# M510X.net
KiCad netlist of a schematic drawn in EAGLE
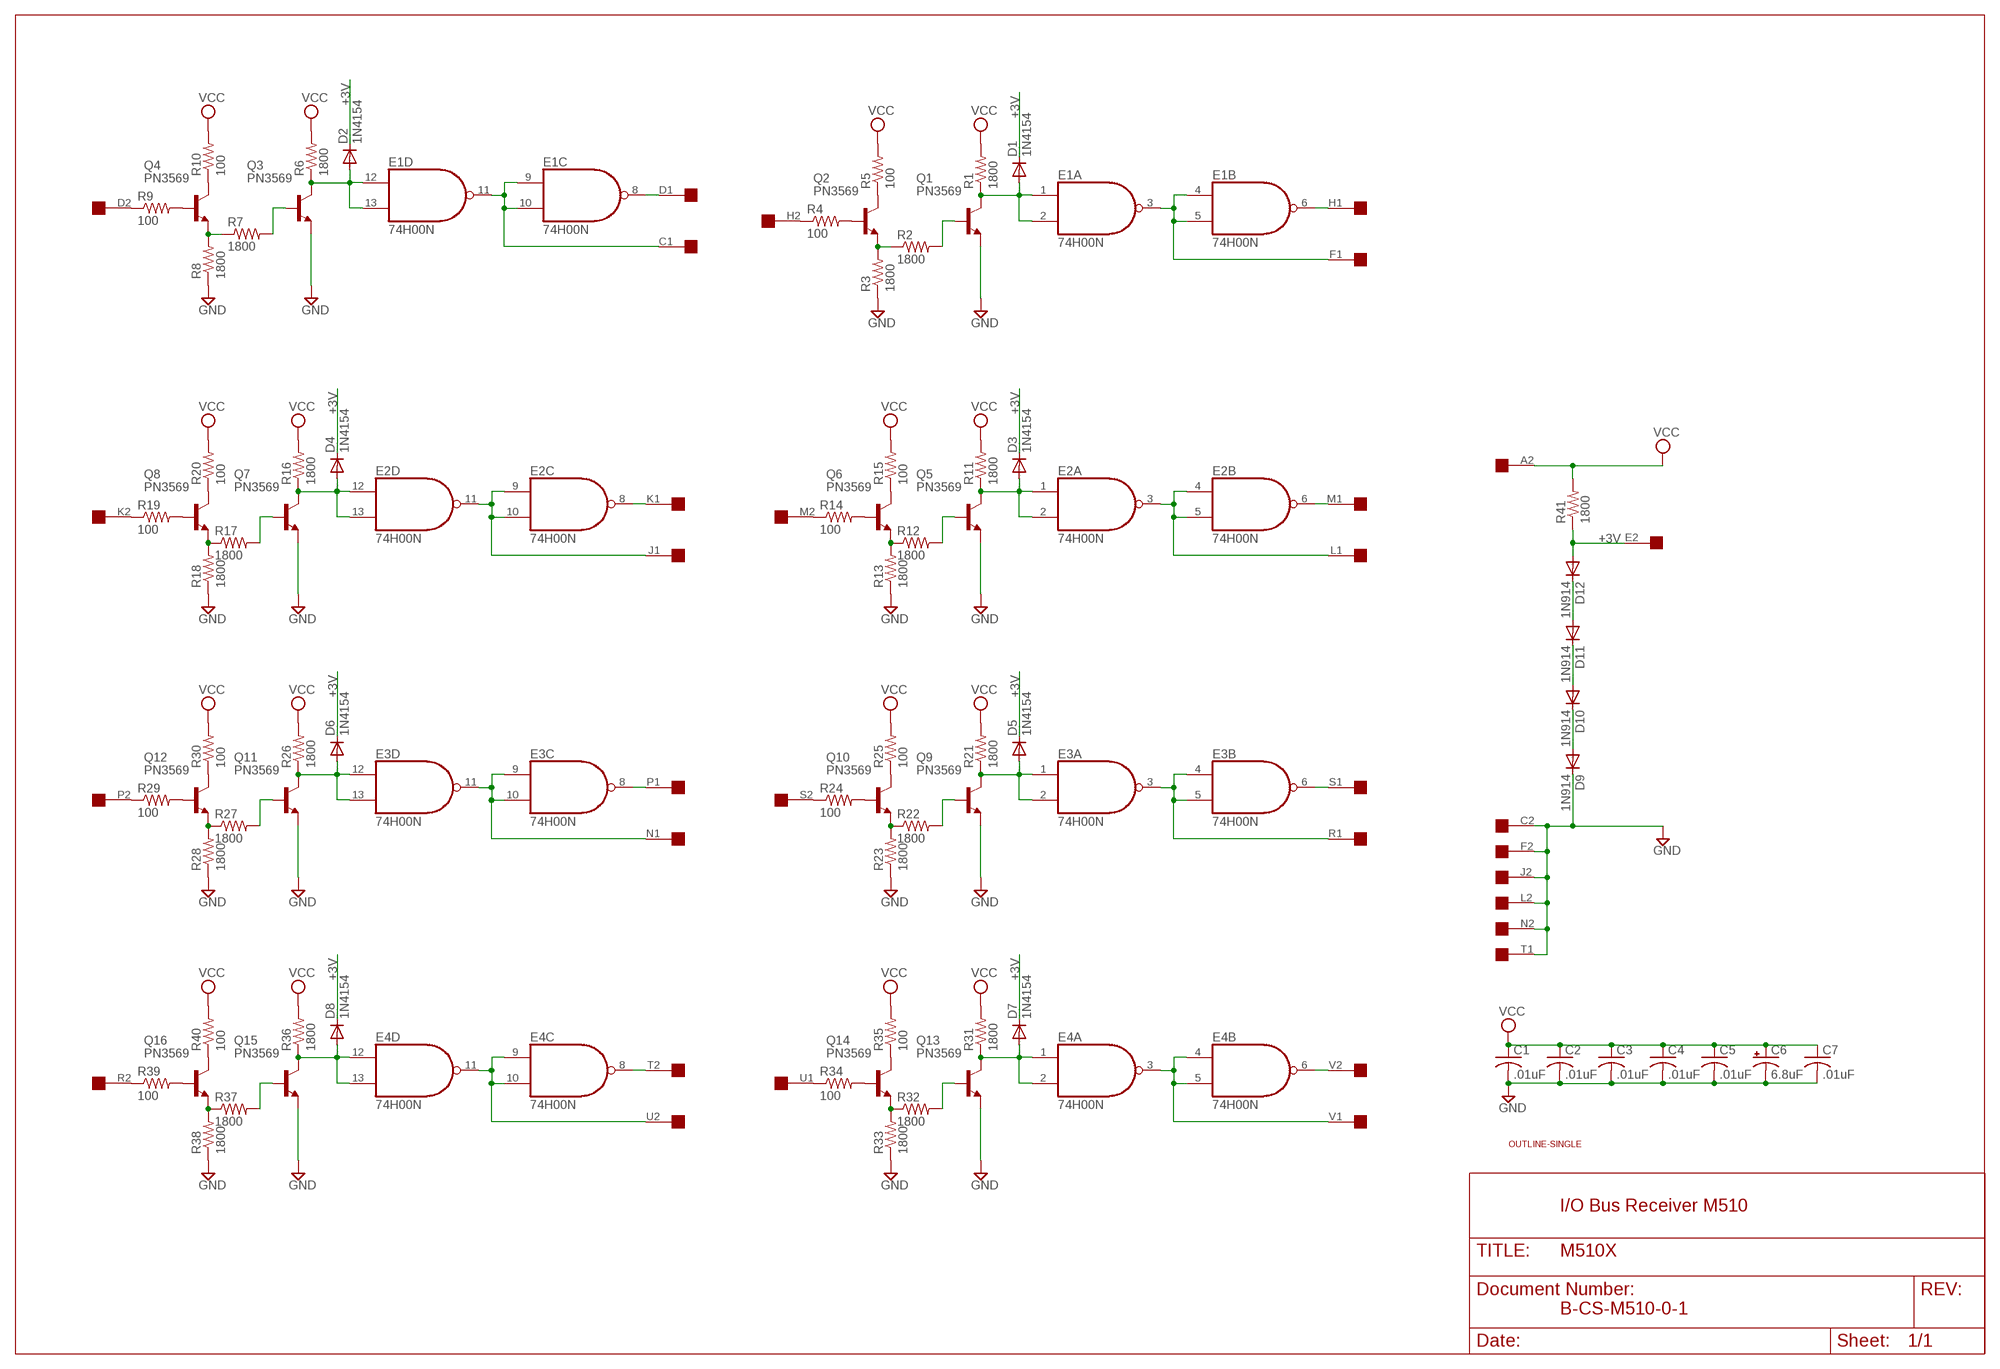
[diagram p0: schematic, sheet 1]

(export (version "E")
  (design (tool "Eeschema 10.0.6"))
  (components
    (comp (ref "C1")
      (value ".01uF")
      (footprint "eagle-import:C050-025X075")
      (libsource (lib "eagle-import") (part "C-US050-025X075"))
    )
    (comp (ref "C2")
      (value ".01uF")
      (footprint "eagle-import:C050-025X075")
      (libsource (lib "eagle-import") (part "C-US050-025X075"))
    )
    (comp (ref "C3")
      (value ".01uF")
      (footprint "eagle-import:C050-025X075")
      (libsource (lib "eagle-import") (part "C-US050-025X075"))
    )
    (comp (ref "C4")
      (value ".01uF")
      (footprint "eagle-import:C050-025X075")
      (libsource (lib "eagle-import") (part "C-US050-025X075"))
    )
    (comp (ref "C5")
      (value ".01uF")
      (footprint "eagle-import:C050-025X075")
      (libsource (lib "eagle-import") (part "C-US050-025X075"))
    )
    (comp (ref "C6")
      (value "6.8uF")
      (footprint "eagle-import:E12-8")
      (libsource (lib "eagle-import") (part "CPOL-USE20-8AXIAL"))
    )
    (comp (ref "C7")
      (value ".01uF")
      (footprint "eagle-import:C050-025X075")
      (libsource (lib "eagle-import") (part "C-US050-025X075"))
    )
    (comp (ref "D1")
      (value "1N4154")
      (footprint "eagle-import:DO35-10")
      (libsource (lib "eagle-import") (part "1N4148DO35-10"))
    )
    (comp (ref "D2")
      (value "1N4154")
      (footprint "eagle-import:DO35-10")
      (libsource (lib "eagle-import") (part "1N4148DO35-10"))
    )
    (comp (ref "D3")
      (value "1N4154")
      (footprint "eagle-import:DO35-10")
      (libsource (lib "eagle-import") (part "1N4148DO35-10"))
    )
    (comp (ref "D4")
      (value "1N4154")
      (footprint "eagle-import:DO35-10")
      (libsource (lib "eagle-import") (part "1N4148DO35-10"))
    )
    (comp (ref "D5")
      (value "1N4154")
      (footprint "eagle-import:DO35-10")
      (libsource (lib "eagle-import") (part "1N4148DO35-10"))
    )
    (comp (ref "D6")
      (value "1N4154")
      (footprint "eagle-import:DO35-10")
      (libsource (lib "eagle-import") (part "1N4148DO35-10"))
    )
    (comp (ref "D7")
      (value "1N4154")
      (footprint "eagle-import:DO35-10")
      (libsource (lib "eagle-import") (part "1N4148DO35-10"))
    )
    (comp (ref "D8")
      (value "1N4154")
      (footprint "eagle-import:DO35-10")
      (libsource (lib "eagle-import") (part "1N4148DO35-10"))
    )
    (comp (ref "D9")
      (value "1N914")
      (footprint "eagle-import:DO35-10")
      (libsource (lib "eagle-import") (part "1N4148DO35-10"))
    )
    (comp (ref "D10")
      (value "1N914")
      (footprint "eagle-import:DO35-10")
      (libsource (lib "eagle-import") (part "1N4148DO35-10"))
    )
    (comp (ref "D11")
      (value "1N914")
      (footprint "eagle-import:DO35-10")
      (libsource (lib "eagle-import") (part "1N4148DO35-10"))
    )
    (comp (ref "D12")
      (value "1N914")
      (footprint "eagle-import:DO35-10")
      (libsource (lib "eagle-import") (part "1N4148DO35-10"))
    )
    (comp (ref "E1")
      (value "74H00N")
      (footprint "eagle-import:DIL14")
      (libsource (lib "eagle-import") (part "7400N"))
    )
    (comp (ref "E2")
      (value "74H00N")
      (footprint "eagle-import:DIL14")
      (libsource (lib "eagle-import") (part "7400N"))
    )
    (comp (ref "E3")
      (value "74H00N")
      (footprint "eagle-import:DIL14")
      (libsource (lib "eagle-import") (part "7400N"))
    )
    (comp (ref "E4")
      (value "74H00N")
      (footprint "eagle-import:DIL14")
      (libsource (lib "eagle-import") (part "7400N"))
    )
    (comp (ref "EDGE1")
      (value "EDGE-2CONNECTOR")
      (footprint "eagle-import:EDGE-CON2")
      (libsource (lib "eagle-import") (part "EDGE-2CONNECTOR"))
    )
    (comp (ref "Q1")
      (value "PN3569")
      (footprint "eagle-import:TO39")
      (libsource (lib "eagle-import") (part "2N3019"))
    )
    (comp (ref "Q2")
      (value "PN3569")
      (footprint "eagle-import:TO39")
      (libsource (lib "eagle-import") (part "2N3019"))
    )
    (comp (ref "Q3")
      (value "PN3569")
      (footprint "eagle-import:TO39")
      (libsource (lib "eagle-import") (part "2N3019"))
    )
    (comp (ref "Q4")
      (value "PN3569")
      (footprint "eagle-import:TO39")
      (libsource (lib "eagle-import") (part "2N3019"))
    )
    (comp (ref "Q5")
      (value "PN3569")
      (footprint "eagle-import:TO39")
      (libsource (lib "eagle-import") (part "2N3019"))
    )
    (comp (ref "Q6")
      (value "PN3569")
      (footprint "eagle-import:TO39")
      (libsource (lib "eagle-import") (part "2N3019"))
    )
    (comp (ref "Q7")
      (value "PN3569")
      (footprint "eagle-import:TO39")
      (libsource (lib "eagle-import") (part "2N3019"))
    )
    (comp (ref "Q8")
      (value "PN3569")
      (footprint "eagle-import:TO39")
      (libsource (lib "eagle-import") (part "2N3019"))
    )
    (comp (ref "Q9")
      (value "PN3569")
      (footprint "eagle-import:TO39")
      (libsource (lib "eagle-import") (part "2N3019"))
    )
    (comp (ref "Q10")
      (value "PN3569")
      (footprint "eagle-import:TO39")
      (libsource (lib "eagle-import") (part "2N3019"))
    )
    (comp (ref "Q11")
      (value "PN3569")
      (footprint "eagle-import:TO39")
      (libsource (lib "eagle-import") (part "2N3019"))
    )
    (comp (ref "Q12")
      (value "PN3569")
      (footprint "eagle-import:TO39")
      (libsource (lib "eagle-import") (part "2N3019"))
    )
    (comp (ref "Q13")
      (value "PN3569")
      (footprint "eagle-import:TO39")
      (libsource (lib "eagle-import") (part "2N3019"))
    )
    (comp (ref "Q14")
      (value "PN3569")
      (footprint "eagle-import:TO39")
      (libsource (lib "eagle-import") (part "2N3019"))
    )
    (comp (ref "Q15")
      (value "PN3569")
      (footprint "eagle-import:TO39")
      (libsource (lib "eagle-import") (part "2N3019"))
    )
    (comp (ref "Q16")
      (value "PN3569")
      (footprint "eagle-import:TO39")
      (libsource (lib "eagle-import") (part "2N3019"))
    )
    (comp (ref "R1")
      (value "1800")
      (footprint "eagle-import:0207_10")
      (libsource (lib "eagle-import") (part "R-US_0207/10"))
    )
    (comp (ref "R2")
      (value "1800")
      (footprint "eagle-import:0207_10")
      (libsource (lib "eagle-import") (part "R-US_0207/10"))
    )
    (comp (ref "R3")
      (value "1800")
      (footprint "eagle-import:0207_10")
      (libsource (lib "eagle-import") (part "R-US_0207/10"))
    )
    (comp (ref "R4")
      (value "100")
      (footprint "eagle-import:0207_10")
      (libsource (lib "eagle-import") (part "R-US_0207/10"))
    )
    (comp (ref "R5")
      (value "100")
      (footprint "eagle-import:0207_10")
      (libsource (lib "eagle-import") (part "R-US_0207/10"))
    )
    (comp (ref "R6")
      (value "1800")
      (footprint "eagle-import:0207_10")
      (libsource (lib "eagle-import") (part "R-US_0207/10"))
    )
    (comp (ref "R7")
      (value "1800")
      (footprint "eagle-import:0207_10")
      (libsource (lib "eagle-import") (part "R-US_0207/10"))
    )
    (comp (ref "R8")
      (value "1800")
      (footprint "eagle-import:0207_10")
      (libsource (lib "eagle-import") (part "R-US_0207/10"))
    )
    (comp (ref "R9")
      (value "100")
      (footprint "eagle-import:0207_10")
      (libsource (lib "eagle-import") (part "R-US_0207/10"))
    )
    (comp (ref "R10")
      (value "100")
      (footprint "eagle-import:0207_10")
      (libsource (lib "eagle-import") (part "R-US_0207/10"))
    )
    (comp (ref "R11")
      (value "1800")
      (footprint "eagle-import:0207_10")
      (libsource (lib "eagle-import") (part "R-US_0207/10"))
    )
    (comp (ref "R12")
      (value "1800")
      (footprint "eagle-import:0207_10")
      (libsource (lib "eagle-import") (part "R-US_0207/10"))
    )
    (comp (ref "R13")
      (value "1800")
      (footprint "eagle-import:0207_10")
      (libsource (lib "eagle-import") (part "R-US_0207/10"))
    )
    (comp (ref "R14")
      (value "100")
      (footprint "eagle-import:0207_10")
      (libsource (lib "eagle-import") (part "R-US_0207/10"))
    )
    (comp (ref "R15")
      (value "100")
      (footprint "eagle-import:0207_10")
      (libsource (lib "eagle-import") (part "R-US_0207/10"))
    )
    (comp (ref "R16")
      (value "1800")
      (footprint "eagle-import:0207_10")
      (libsource (lib "eagle-import") (part "R-US_0207/10"))
    )
    (comp (ref "R17")
      (value "1800")
      (footprint "eagle-import:0207_10")
      (libsource (lib "eagle-import") (part "R-US_0207/10"))
    )
    (comp (ref "R18")
      (value "1800")
      (footprint "eagle-import:0207_10")
      (libsource (lib "eagle-import") (part "R-US_0207/10"))
    )
    (comp (ref "R19")
      (value "100")
      (footprint "eagle-import:0207_10")
      (libsource (lib "eagle-import") (part "R-US_0207/10"))
    )
    (comp (ref "R20")
      (value "100")
      (footprint "eagle-import:0207_10")
      (libsource (lib "eagle-import") (part "R-US_0207/10"))
    )
    (comp (ref "R21")
      (value "1800")
      (footprint "eagle-import:0207_10")
      (libsource (lib "eagle-import") (part "R-US_0207/10"))
    )
    (comp (ref "R22")
      (value "1800")
      (footprint "eagle-import:0207_10")
      (libsource (lib "eagle-import") (part "R-US_0207/10"))
    )
    (comp (ref "R23")
      (value "1800")
      (footprint "eagle-import:0207_10")
      (libsource (lib "eagle-import") (part "R-US_0207/10"))
    )
    (comp (ref "R24")
      (value "100")
      (footprint "eagle-import:0207_10")
      (libsource (lib "eagle-import") (part "R-US_0207/10"))
    )
    (comp (ref "R25")
      (value "100")
      (footprint "eagle-import:0207_10")
      (libsource (lib "eagle-import") (part "R-US_0207/10"))
    )
    (comp (ref "R26")
      (value "1800")
      (footprint "eagle-import:0207_10")
      (libsource (lib "eagle-import") (part "R-US_0207/10"))
    )
    (comp (ref "R27")
      (value "1800")
      (footprint "eagle-import:0207_10")
      (libsource (lib "eagle-import") (part "R-US_0207/10"))
    )
    (comp (ref "R28")
      (value "1800")
      (footprint "eagle-import:0207_10")
      (libsource (lib "eagle-import") (part "R-US_0207/10"))
    )
    (comp (ref "R29")
      (value "100")
      (footprint "eagle-import:0207_10")
      (libsource (lib "eagle-import") (part "R-US_0207/10"))
    )
    (comp (ref "R30")
      (value "100")
      (footprint "eagle-import:0207_10")
      (libsource (lib "eagle-import") (part "R-US_0207/10"))
    )
    (comp (ref "R31")
      (value "1800")
      (footprint "eagle-import:0207_10")
      (libsource (lib "eagle-import") (part "R-US_0207/10"))
    )
    (comp (ref "R32")
      (value "1800")
      (footprint "eagle-import:0207_10")
      (libsource (lib "eagle-import") (part "R-US_0207/10"))
    )
    (comp (ref "R33")
      (value "1800")
      (footprint "eagle-import:0207_10")
      (libsource (lib "eagle-import") (part "R-US_0207/10"))
    )
    (comp (ref "R34")
      (value "100")
      (footprint "eagle-import:0207_10")
      (libsource (lib "eagle-import") (part "R-US_0207/10"))
    )
    (comp (ref "R35")
      (value "100")
      (footprint "eagle-import:0207_10")
      (libsource (lib "eagle-import") (part "R-US_0207/10"))
    )
    (comp (ref "R36")
      (value "1800")
      (footprint "eagle-import:0207_10")
      (libsource (lib "eagle-import") (part "R-US_0207/10"))
    )
    (comp (ref "R37")
      (value "1800")
      (footprint "eagle-import:0207_10")
      (libsource (lib "eagle-import") (part "R-US_0207/10"))
    )
    (comp (ref "R38")
      (value "1800")
      (footprint "eagle-import:0207_10")
      (libsource (lib "eagle-import") (part "R-US_0207/10"))
    )
    (comp (ref "R39")
      (value "100")
      (footprint "eagle-import:0207_10")
      (libsource (lib "eagle-import") (part "R-US_0207/10"))
    )
    (comp (ref "R40")
      (value "100")
      (footprint "eagle-import:0207_10")
      (libsource (lib "eagle-import") (part "R-US_0207/10"))
    )
    (comp (ref "R41")
      (value "1800")
      (footprint "eagle-import:0207_10")
      (libsource (lib "eagle-import") (part "R-US_0207/10"))
    )
    (comp (ref "U$4")
      (value "OUTLINE-SINGLE")
      (footprint "eagle-import:SINGLE")
      (libsource (lib "eagle-import") (part "OUTLINE-SINGLE"))
    )
  )
  (nets
    (net (code "1") (name "/+3V") (class "Default")
      (node (ref "D1") (pin "C") (pinfunction "C_C") (pintype "passive"))
      (node (ref "D12") (pin "A") (pinfunction "A_A") (pintype "passive"))
      (node (ref "D2") (pin "C") (pinfunction "C_C") (pintype "passive"))
      (node (ref "D3") (pin "C") (pinfunction "C_C") (pintype "passive"))
      (node (ref "D4") (pin "C") (pinfunction "C_C") (pintype "passive"))
      (node (ref "D5") (pin "C") (pinfunction "C_C") (pintype "passive"))
      (node (ref "D6") (pin "C") (pinfunction "C_C") (pintype "passive"))
      (node (ref "D7") (pin "C") (pinfunction "C_C") (pintype "passive"))
      (node (ref "D8") (pin "C") (pinfunction "C_C") (pintype "passive"))
      (node (ref "EDGE1") (pin "E2") (pinfunction "1_E2") (pintype "bidirectional"))
      (node (ref "R41") (pin "1") (pinfunction "1_1") (pintype "passive"))
    )
    (net (code "2") (name "GND") (class "Default")
      (node (ref "C1") (pin "2") (pinfunction "2_2") (pintype "passive"))
      (node (ref "C2") (pin "2") (pinfunction "2_2") (pintype "passive"))
      (node (ref "C3") (pin "2") (pinfunction "2_2") (pintype "passive"))
      (node (ref "C4") (pin "2") (pinfunction "2_2") (pintype "passive"))
      (node (ref "C5") (pin "2") (pinfunction "2_2") (pintype "passive"))
      (node (ref "C6") (pin "-") (pinfunction "-_-") (pintype "passive"))
      (node (ref "C7") (pin "2") (pinfunction "2_2") (pintype "passive"))
      (node (ref "D9") (pin "C") (pinfunction "C_C") (pintype "passive"))
      (node (ref "EDGE1") (pin "C2") (pinfunction "1_C2") (pintype "bidirectional"))
      (node (ref "EDGE1") (pin "F2") (pinfunction "1_F2") (pintype "bidirectional"))
      (node (ref "EDGE1") (pin "J2") (pinfunction "1_J2") (pintype "bidirectional"))
      (node (ref "EDGE1") (pin "L2") (pinfunction "1_L2") (pintype "bidirectional"))
      (node (ref "EDGE1") (pin "N2") (pinfunction "1_N2") (pintype "bidirectional"))
      (node (ref "EDGE1") (pin "T1") (pinfunction "1_T1") (pintype "bidirectional"))
      (node (ref "Q1") (pin "1") (pinfunction "E_1") (pintype "passive"))
      (node (ref "Q11") (pin "1") (pinfunction "E_1") (pintype "passive"))
      (node (ref "Q13") (pin "1") (pinfunction "E_1") (pintype "passive"))
      (node (ref "Q15") (pin "1") (pinfunction "E_1") (pintype "passive"))
      (node (ref "Q3") (pin "1") (pinfunction "E_1") (pintype "passive"))
      (node (ref "Q5") (pin "1") (pinfunction "E_1") (pintype "passive"))
      (node (ref "Q7") (pin "1") (pinfunction "E_1") (pintype "passive"))
      (node (ref "Q9") (pin "1") (pinfunction "E_1") (pintype "passive"))
      (node (ref "R13") (pin "1") (pinfunction "1_1") (pintype "passive"))
      (node (ref "R18") (pin "1") (pinfunction "1_1") (pintype "passive"))
      (node (ref "R23") (pin "1") (pinfunction "1_1") (pintype "passive"))
      (node (ref "R28") (pin "1") (pinfunction "1_1") (pintype "passive"))
      (node (ref "R3") (pin "1") (pinfunction "1_1") (pintype "passive"))
      (node (ref "R33") (pin "1") (pinfunction "1_1") (pintype "passive"))
      (node (ref "R38") (pin "1") (pinfunction "1_1") (pintype "passive"))
      (node (ref "R8") (pin "1") (pinfunction "1_1") (pintype "passive"))
    )
    (net (code "3") (name "Net-(D10-PadA)") (class "Default")
      (node (ref "D10") (pin "A") (pinfunction "A_A") (pintype "passive"))
      (node (ref "D11") (pin "C") (pinfunction "C_C") (pintype "passive"))
    )
    (net (code "4") (name "Net-(D10-PadC)") (class "Default")
      (node (ref "D10") (pin "C") (pinfunction "C_C") (pintype "passive"))
      (node (ref "D9") (pin "A") (pinfunction "A_A") (pintype "passive"))
    )
    (net (code "5") (name "Net-(D11-PadA)") (class "Default")
      (node (ref "D11") (pin "A") (pinfunction "A_A") (pintype "passive"))
      (node (ref "D12") (pin "C") (pinfunction "C_C") (pintype "passive"))
    )
    (net (code "6") (name "Net-(E1A-I0)") (class "Default")
      (node (ref "D1") (pin "A") (pinfunction "A_A") (pintype "passive"))
      (node (ref "E1") (pin "1") (pinfunction "I0_1") (pintype "input"))
      (node (ref "E1") (pin "2") (pinfunction "I1_2") (pintype "input"))
      (node (ref "Q1") (pin "3") (pinfunction "C_3") (pintype "passive"))
      (node (ref "R1") (pin "1") (pinfunction "1_1") (pintype "passive"))
    )
    (net (code "7") (name "Net-(E1A-O)") (class "Default")
      (node (ref "E1") (pin "3") (pinfunction "O_3") (pintype "output"))
      (node (ref "E1") (pin "4") (pinfunction "I0_4") (pintype "input"))
      (node (ref "E1") (pin "5") (pinfunction "I1_5") (pintype "input"))
      (node (ref "EDGE1") (pin "F1") (pinfunction "1_F1") (pintype "bidirectional"))
    )
    (net (code "8") (name "Net-(E1B-O)") (class "Default")
      (node (ref "E1") (pin "6") (pinfunction "O_6") (pintype "output"))
      (node (ref "EDGE1") (pin "H1") (pinfunction "1_H1") (pintype "bidirectional"))
    )
    (net (code "9") (name "Net-(E1C-I0)") (class "Default")
      (node (ref "E1") (pin "10") (pinfunction "I1_10") (pintype "input"))
      (node (ref "E1") (pin "11") (pinfunction "O_11") (pintype "output"))
      (node (ref "E1") (pin "9") (pinfunction "I0_9") (pintype "input"))
      (node (ref "EDGE1") (pin "C1") (pinfunction "1_C1") (pintype "bidirectional"))
    )
    (net (code "10") (name "Net-(E1C-O)") (class "Default")
      (node (ref "E1") (pin "8") (pinfunction "O_8") (pintype "output"))
      (node (ref "EDGE1") (pin "D1") (pinfunction "1_D1") (pintype "bidirectional"))
    )
    (net (code "11") (name "Net-(E1D-I0)") (class "Default")
      (node (ref "D2") (pin "A") (pinfunction "A_A") (pintype "passive"))
      (node (ref "E1") (pin "12") (pinfunction "I0_12") (pintype "input"))
      (node (ref "E1") (pin "13") (pinfunction "I1_13") (pintype "input"))
      (node (ref "Q3") (pin "3") (pinfunction "C_3") (pintype "passive"))
      (node (ref "R6") (pin "1") (pinfunction "1_1") (pintype "passive"))
    )
    (net (code "12") (name "Net-(E2A-I0)") (class "Default")
      (node (ref "D3") (pin "A") (pinfunction "A_A") (pintype "passive"))
      (node (ref "E2") (pin "1") (pinfunction "I0_1") (pintype "input"))
      (node (ref "E2") (pin "2") (pinfunction "I1_2") (pintype "input"))
      (node (ref "Q5") (pin "3") (pinfunction "C_3") (pintype "passive"))
      (node (ref "R11") (pin "1") (pinfunction "1_1") (pintype "passive"))
    )
    (net (code "13") (name "Net-(E2A-O)") (class "Default")
      (node (ref "E2") (pin "3") (pinfunction "O_3") (pintype "output"))
      (node (ref "E2") (pin "4") (pinfunction "I0_4") (pintype "input"))
      (node (ref "E2") (pin "5") (pinfunction "I1_5") (pintype "input"))
      (node (ref "EDGE1") (pin "L1") (pinfunction "1_L1") (pintype "bidirectional"))
    )
    (net (code "14") (name "Net-(E2B-O)") (class "Default")
      (node (ref "E2") (pin "6") (pinfunction "O_6") (pintype "output"))
      (node (ref "EDGE1") (pin "M1") (pinfunction "1_M1") (pintype "bidirectional"))
    )
    (net (code "15") (name "Net-(E2C-I0)") (class "Default")
      (node (ref "E2") (pin "10") (pinfunction "I1_10") (pintype "input"))
      (node (ref "E2") (pin "11") (pinfunction "O_11") (pintype "output"))
      (node (ref "E2") (pin "9") (pinfunction "I0_9") (pintype "input"))
      (node (ref "EDGE1") (pin "J1") (pinfunction "1_J1") (pintype "bidirectional"))
    )
    (net (code "16") (name "Net-(E2C-O)") (class "Default")
      (node (ref "E2") (pin "8") (pinfunction "O_8") (pintype "output"))
      (node (ref "EDGE1") (pin "K1") (pinfunction "1_K1") (pintype "bidirectional"))
    )
    (net (code "17") (name "Net-(E2D-I0)") (class "Default")
      (node (ref "D4") (pin "A") (pinfunction "A_A") (pintype "passive"))
      (node (ref "E2") (pin "12") (pinfunction "I0_12") (pintype "input"))
      (node (ref "E2") (pin "13") (pinfunction "I1_13") (pintype "input"))
      (node (ref "Q7") (pin "3") (pinfunction "C_3") (pintype "passive"))
      (node (ref "R16") (pin "1") (pinfunction "1_1") (pintype "passive"))
    )
    (net (code "18") (name "Net-(E3A-I0)") (class "Default")
      (node (ref "D5") (pin "A") (pinfunction "A_A") (pintype "passive"))
      (node (ref "E3") (pin "1") (pinfunction "I0_1") (pintype "input"))
      (node (ref "E3") (pin "2") (pinfunction "I1_2") (pintype "input"))
      (node (ref "Q9") (pin "3") (pinfunction "C_3") (pintype "passive"))
      (node (ref "R21") (pin "1") (pinfunction "1_1") (pintype "passive"))
    )
    (net (code "19") (name "Net-(E3A-O)") (class "Default")
      (node (ref "E3") (pin "3") (pinfunction "O_3") (pintype "output"))
      (node (ref "E3") (pin "4") (pinfunction "I0_4") (pintype "input"))
      (node (ref "E3") (pin "5") (pinfunction "I1_5") (pintype "input"))
      (node (ref "EDGE1") (pin "R1") (pinfunction "1_R1") (pintype "bidirectional"))
    )
    (net (code "20") (name "Net-(E3B-O)") (class "Default")
      (node (ref "E3") (pin "6") (pinfunction "O_6") (pintype "output"))
      (node (ref "EDGE1") (pin "S1") (pinfunction "1_S1") (pintype "bidirectional"))
    )
    (net (code "21") (name "Net-(E3C-I0)") (class "Default")
      (node (ref "E3") (pin "10") (pinfunction "I1_10") (pintype "input"))
      (node (ref "E3") (pin "11") (pinfunction "O_11") (pintype "output"))
      (node (ref "E3") (pin "9") (pinfunction "I0_9") (pintype "input"))
      (node (ref "EDGE1") (pin "N1") (pinfunction "1_N1") (pintype "bidirectional"))
    )
    (net (code "22") (name "Net-(E3C-O)") (class "Default")
      (node (ref "E3") (pin "8") (pinfunction "O_8") (pintype "output"))
      (node (ref "EDGE1") (pin "P1") (pinfunction "1_P1") (pintype "bidirectional"))
    )
    (net (code "23") (name "Net-(E3D-I0)") (class "Default")
      (node (ref "D6") (pin "A") (pinfunction "A_A") (pintype "passive"))
      (node (ref "E3") (pin "12") (pinfunction "I0_12") (pintype "input"))
      (node (ref "E3") (pin "13") (pinfunction "I1_13") (pintype "input"))
      (node (ref "Q11") (pin "3") (pinfunction "C_3") (pintype "passive"))
      (node (ref "R26") (pin "1") (pinfunction "1_1") (pintype "passive"))
    )
    (net (code "24") (name "Net-(E4A-I0)") (class "Default")
      (node (ref "D7") (pin "A") (pinfunction "A_A") (pintype "passive"))
      (node (ref "E4") (pin "1") (pinfunction "I0_1") (pintype "input"))
      (node (ref "E4") (pin "2") (pinfunction "I1_2") (pintype "input"))
      (node (ref "Q13") (pin "3") (pinfunction "C_3") (pintype "passive"))
      (node (ref "R31") (pin "1") (pinfunction "1_1") (pintype "passive"))
    )
    (net (code "25") (name "Net-(E4A-O)") (class "Default")
      (node (ref "E4") (pin "3") (pinfunction "O_3") (pintype "output"))
      (node (ref "E4") (pin "4") (pinfunction "I0_4") (pintype "input"))
      (node (ref "E4") (pin "5") (pinfunction "I1_5") (pintype "input"))
      (node (ref "EDGE1") (pin "V1") (pinfunction "1_V1") (pintype "bidirectional"))
    )
    (net (code "26") (name "Net-(E4B-O)") (class "Default")
      (node (ref "E4") (pin "6") (pinfunction "O_6") (pintype "output"))
      (node (ref "EDGE1") (pin "V2") (pinfunction "1_V2") (pintype "bidirectional"))
    )
    (net (code "27") (name "Net-(E4C-I0)") (class "Default")
      (node (ref "E4") (pin "10") (pinfunction "I1_10") (pintype "input"))
      (node (ref "E4") (pin "11") (pinfunction "O_11") (pintype "output"))
      (node (ref "E4") (pin "9") (pinfunction "I0_9") (pintype "input"))
      (node (ref "EDGE1") (pin "U2") (pinfunction "1_U2") (pintype "bidirectional"))
    )
    (net (code "28") (name "Net-(E4C-O)") (class "Default")
      (node (ref "E4") (pin "8") (pinfunction "O_8") (pintype "output"))
      (node (ref "EDGE1") (pin "T2") (pinfunction "1_T2") (pintype "bidirectional"))
    )
    (net (code "29") (name "Net-(E4D-I0)") (class "Default")
      (node (ref "D8") (pin "A") (pinfunction "A_A") (pintype "passive"))
      (node (ref "E4") (pin "12") (pinfunction "I0_12") (pintype "input"))
      (node (ref "E4") (pin "13") (pinfunction "I1_13") (pintype "input"))
      (node (ref "Q15") (pin "3") (pinfunction "C_3") (pintype "passive"))
      (node (ref "R36") (pin "1") (pinfunction "1_1") (pintype "passive"))
    )
    (net (code "30") (name "Net-(EDGE1AB-1)") (class "Default")
      (node (ref "EDGE1") (pin "R2") (pinfunction "1_R2") (pintype "bidirectional"))
      (node (ref "R39") (pin "1") (pinfunction "1_1") (pintype "passive"))
    )
    (net (code "31") (name "Net-(EDGE1AD-1)") (class "Default")
      (node (ref "EDGE1") (pin "S2") (pinfunction "1_S2") (pintype "bidirectional"))
      (node (ref "R24") (pin "1") (pinfunction "1_1") (pintype "passive"))
    )
    (net (code "32") (name "Net-(EDGE1AG-1)") (class "Default")
      (node (ref "EDGE1") (pin "U1") (pinfunction "1_U1") (pintype "bidirectional"))
      (node (ref "R34") (pin "1") (pinfunction "1_1") (pintype "passive"))
    )
    (net (code "33") (name "Net-(EDGE1H-1)") (class "Default")
      (node (ref "EDGE1") (pin "D2") (pinfunction "1_D2") (pintype "bidirectional"))
      (node (ref "R9") (pin "1") (pinfunction "1_1") (pintype "passive"))
    )
    (net (code "34") (name "Net-(EDGE1N-1)") (class "Default")
      (node (ref "EDGE1") (pin "H2") (pinfunction "1_H2") (pintype "bidirectional"))
      (node (ref "R4") (pin "1") (pinfunction "1_1") (pintype "passive"))
    )
    (net (code "35") (name "Net-(EDGE1R-1)") (class "Default")
      (node (ref "EDGE1") (pin "K2") (pinfunction "1_K2") (pintype "bidirectional"))
      (node (ref "R19") (pin "1") (pinfunction "1_1") (pintype "passive"))
    )
    (net (code "36") (name "Net-(EDGE1V-1)") (class "Default")
      (node (ref "EDGE1") (pin "M2") (pinfunction "1_M2") (pintype "bidirectional"))
      (node (ref "R14") (pin "1") (pinfunction "1_1") (pintype "passive"))
    )
    (net (code "37") (name "Net-(EDGE1Z-1)") (class "Default")
      (node (ref "EDGE1") (pin "P2") (pinfunction "1_P2") (pintype "bidirectional"))
      (node (ref "R29") (pin "1") (pinfunction "1_1") (pintype "passive"))
    )
    (net (code "38") (name "Net-(Q1-B)") (class "Default")
      (node (ref "Q1") (pin "2") (pinfunction "B_2") (pintype "passive"))
      (node (ref "R2") (pin "2") (pinfunction "2_2") (pintype "passive"))
    )
    (net (code "39") (name "Net-(Q2-B)") (class "Default")
      (node (ref "Q2") (pin "2") (pinfunction "B_2") (pintype "passive"))
      (node (ref "R4") (pin "2") (pinfunction "2_2") (pintype "passive"))
    )
    (net (code "40") (name "Net-(Q2-C)") (class "Default")
      (node (ref "Q2") (pin "3") (pinfunction "C_3") (pintype "passive"))
      (node (ref "R5") (pin "1") (pinfunction "1_1") (pintype "passive"))
    )
    (net (code "41") (name "Net-(Q2-E)") (class "Default")
      (node (ref "Q2") (pin "1") (pinfunction "E_1") (pintype "passive"))
      (node (ref "R2") (pin "1") (pinfunction "1_1") (pintype "passive"))
      (node (ref "R3") (pin "2") (pinfunction "2_2") (pintype "passive"))
    )
    (net (code "42") (name "Net-(Q3-B)") (class "Default")
      (node (ref "Q3") (pin "2") (pinfunction "B_2") (pintype "passive"))
      (node (ref "R7") (pin "2") (pinfunction "2_2") (pintype "passive"))
    )
    (net (code "43") (name "Net-(Q4-B)") (class "Default")
      (node (ref "Q4") (pin "2") (pinfunction "B_2") (pintype "passive"))
      (node (ref "R9") (pin "2") (pinfunction "2_2") (pintype "passive"))
    )
    (net (code "44") (name "Net-(Q4-C)") (class "Default")
      (node (ref "Q4") (pin "3") (pinfunction "C_3") (pintype "passive"))
      (node (ref "R10") (pin "1") (pinfunction "1_1") (pintype "passive"))
    )
    (net (code "45") (name "Net-(Q4-E)") (class "Default")
      (node (ref "Q4") (pin "1") (pinfunction "E_1") (pintype "passive"))
      (node (ref "R7") (pin "1") (pinfunction "1_1") (pintype "passive"))
      (node (ref "R8") (pin "2") (pinfunction "2_2") (pintype "passive"))
    )
    (net (code "46") (name "Net-(Q5-B)") (class "Default")
      (node (ref "Q5") (pin "2") (pinfunction "B_2") (pintype "passive"))
      (node (ref "R12") (pin "2") (pinfunction "2_2") (pintype "passive"))
    )
    (net (code "47") (name "Net-(Q6-B)") (class "Default")
      (node (ref "Q6") (pin "2") (pinfunction "B_2") (pintype "passive"))
      (node (ref "R14") (pin "2") (pinfunction "2_2") (pintype "passive"))
    )
    (net (code "48") (name "Net-(Q6-C)") (class "Default")
      (node (ref "Q6") (pin "3") (pinfunction "C_3") (pintype "passive"))
      (node (ref "R15") (pin "1") (pinfunction "1_1") (pintype "passive"))
    )
    (net (code "49") (name "Net-(Q6-E)") (class "Default")
      (node (ref "Q6") (pin "1") (pinfunction "E_1") (pintype "passive"))
      (node (ref "R12") (pin "1") (pinfunction "1_1") (pintype "passive"))
      (node (ref "R13") (pin "2") (pinfunction "2_2") (pintype "passive"))
    )
    (net (code "50") (name "Net-(Q7-B)") (class "Default")
      (node (ref "Q7") (pin "2") (pinfunction "B_2") (pintype "passive"))
      (node (ref "R17") (pin "2") (pinfunction "2_2") (pintype "passive"))
    )
    (net (code "51") (name "Net-(Q8-B)") (class "Default")
      (node (ref "Q8") (pin "2") (pinfunction "B_2") (pintype "passive"))
      (node (ref "R19") (pin "2") (pinfunction "2_2") (pintype "passive"))
    )
    (net (code "52") (name "Net-(Q8-C)") (class "Default")
      (node (ref "Q8") (pin "3") (pinfunction "C_3") (pintype "passive"))
      (node (ref "R20") (pin "1") (pinfunction "1_1") (pintype "passive"))
    )
    (net (code "53") (name "Net-(Q8-E)") (class "Default")
      (node (ref "Q8") (pin "1") (pinfunction "E_1") (pintype "passive"))
      (node (ref "R17") (pin "1") (pinfunction "1_1") (pintype "passive"))
      (node (ref "R18") (pin "2") (pinfunction "2_2") (pintype "passive"))
    )
    (net (code "54") (name "Net-(Q9-B)") (class "Default")
      (node (ref "Q9") (pin "2") (pinfunction "B_2") (pintype "passive"))
      (node (ref "R22") (pin "2") (pinfunction "2_2") (pintype "passive"))
    )
    (net (code "55") (name "Net-(Q10-B)") (class "Default")
      (node (ref "Q10") (pin "2") (pinfunction "B_2") (pintype "passive"))
      (node (ref "R24") (pin "2") (pinfunction "2_2") (pintype "passive"))
    )
    (net (code "56") (name "Net-(Q10-C)") (class "Default")
      (node (ref "Q10") (pin "3") (pinfunction "C_3") (pintype "passive"))
      (node (ref "R25") (pin "1") (pinfunction "1_1") (pintype "passive"))
    )
    (net (code "57") (name "Net-(Q10-E)") (class "Default")
      (node (ref "Q10") (pin "1") (pinfunction "E_1") (pintype "passive"))
      (node (ref "R22") (pin "1") (pinfunction "1_1") (pintype "passive"))
      (node (ref "R23") (pin "2") (pinfunction "2_2") (pintype "passive"))
    )
    (net (code "58") (name "Net-(Q11-B)") (class "Default")
      (node (ref "Q11") (pin "2") (pinfunction "B_2") (pintype "passive"))
      (node (ref "R27") (pin "2") (pinfunction "2_2") (pintype "passive"))
    )
    (net (code "59") (name "Net-(Q12-B)") (class "Default")
      (node (ref "Q12") (pin "2") (pinfunction "B_2") (pintype "passive"))
      (node (ref "R29") (pin "2") (pinfunction "2_2") (pintype "passive"))
    )
    (net (code "60") (name "Net-(Q12-C)") (class "Default")
      (node (ref "Q12") (pin "3") (pinfunction "C_3") (pintype "passive"))
      (node (ref "R30") (pin "1") (pinfunction "1_1") (pintype "passive"))
    )
    (net (code "61") (name "Net-(Q12-E)") (class "Default")
      (node (ref "Q12") (pin "1") (pinfunction "E_1") (pintype "passive"))
      (node (ref "R27") (pin "1") (pinfunction "1_1") (pintype "passive"))
      (node (ref "R28") (pin "2") (pinfunction "2_2") (pintype "passive"))
    )
    (net (code "62") (name "Net-(Q13-B)") (class "Default")
      (node (ref "Q13") (pin "2") (pinfunction "B_2") (pintype "passive"))
      (node (ref "R32") (pin "2") (pinfunction "2_2") (pintype "passive"))
    )
    (net (code "63") (name "Net-(Q14-B)") (class "Default")
      (node (ref "Q14") (pin "2") (pinfunction "B_2") (pintype "passive"))
      (node (ref "R34") (pin "2") (pinfunction "2_2") (pintype "passive"))
    )
    (net (code "64") (name "Net-(Q14-C)") (class "Default")
      (node (ref "Q14") (pin "3") (pinfunction "C_3") (pintype "passive"))
      (node (ref "R35") (pin "1") (pinfunction "1_1") (pintype "passive"))
    )
    (net (code "65") (name "Net-(Q14-E)") (class "Default")
      (node (ref "Q14") (pin "1") (pinfunction "E_1") (pintype "passive"))
      (node (ref "R32") (pin "1") (pinfunction "1_1") (pintype "passive"))
      (node (ref "R33") (pin "2") (pinfunction "2_2") (pintype "passive"))
    )
    (net (code "66") (name "Net-(Q15-B)") (class "Default")
      (node (ref "Q15") (pin "2") (pinfunction "B_2") (pintype "passive"))
      (node (ref "R37") (pin "2") (pinfunction "2_2") (pintype "passive"))
    )
    (net (code "67") (name "Net-(Q16-B)") (class "Default")
      (node (ref "Q16") (pin "2") (pinfunction "B_2") (pintype "passive"))
      (node (ref "R39") (pin "2") (pinfunction "2_2") (pintype "passive"))
    )
    (net (code "68") (name "Net-(Q16-C)") (class "Default")
      (node (ref "Q16") (pin "3") (pinfunction "C_3") (pintype "passive"))
      (node (ref "R40") (pin "1") (pinfunction "1_1") (pintype "passive"))
    )
    (net (code "69") (name "Net-(Q16-E)") (class "Default")
      (node (ref "Q16") (pin "1") (pinfunction "E_1") (pintype "passive"))
      (node (ref "R37") (pin "1") (pinfunction "1_1") (pintype "passive"))
      (node (ref "R38") (pin "2") (pinfunction "2_2") (pintype "passive"))
    )
    (net (code "70") (name "VCC") (class "Default")
      (node (ref "C1") (pin "1") (pinfunction "1_1") (pintype "passive"))
      (node (ref "C2") (pin "1") (pinfunction "1_1") (pintype "passive"))
      (node (ref "C3") (pin "1") (pinfunction "1_1") (pintype "passive"))
      (node (ref "C4") (pin "1") (pinfunction "1_1") (pintype "passive"))
      (node (ref "C5") (pin "1") (pinfunction "1_1") (pintype "passive"))
      (node (ref "C6") (pin "+") (pinfunction "+_+") (pintype "passive"))
      (node (ref "C7") (pin "1") (pinfunction "1_1") (pintype "passive"))
      (node (ref "EDGE1") (pin "A2") (pinfunction "1_A2") (pintype "bidirectional"))
      (node (ref "R1") (pin "2") (pinfunction "2_2") (pintype "passive"))
      (node (ref "R10") (pin "2") (pinfunction "2_2") (pintype "passive"))
      (node (ref "R11") (pin "2") (pinfunction "2_2") (pintype "passive"))
      (node (ref "R15") (pin "2") (pinfunction "2_2") (pintype "passive"))
      (node (ref "R16") (pin "2") (pinfunction "2_2") (pintype "passive"))
      (node (ref "R20") (pin "2") (pinfunction "2_2") (pintype "passive"))
      (node (ref "R21") (pin "2") (pinfunction "2_2") (pintype "passive"))
      (node (ref "R25") (pin "2") (pinfunction "2_2") (pintype "passive"))
      (node (ref "R26") (pin "2") (pinfunction "2_2") (pintype "passive"))
      (node (ref "R30") (pin "2") (pinfunction "2_2") (pintype "passive"))
      (node (ref "R31") (pin "2") (pinfunction "2_2") (pintype "passive"))
      (node (ref "R35") (pin "2") (pinfunction "2_2") (pintype "passive"))
      (node (ref "R36") (pin "2") (pinfunction "2_2") (pintype "passive"))
      (node (ref "R40") (pin "2") (pinfunction "2_2") (pintype "passive"))
      (node (ref "R41") (pin "2") (pinfunction "2_2") (pintype "passive"))
      (node (ref "R5") (pin "2") (pinfunction "2_2") (pintype "passive"))
      (node (ref "R6") (pin "2") (pinfunction "2_2") (pintype "passive"))
    )
  )
)
